# basic_circuit.net
KiCad netlist of a schematic drawn in EAGLE
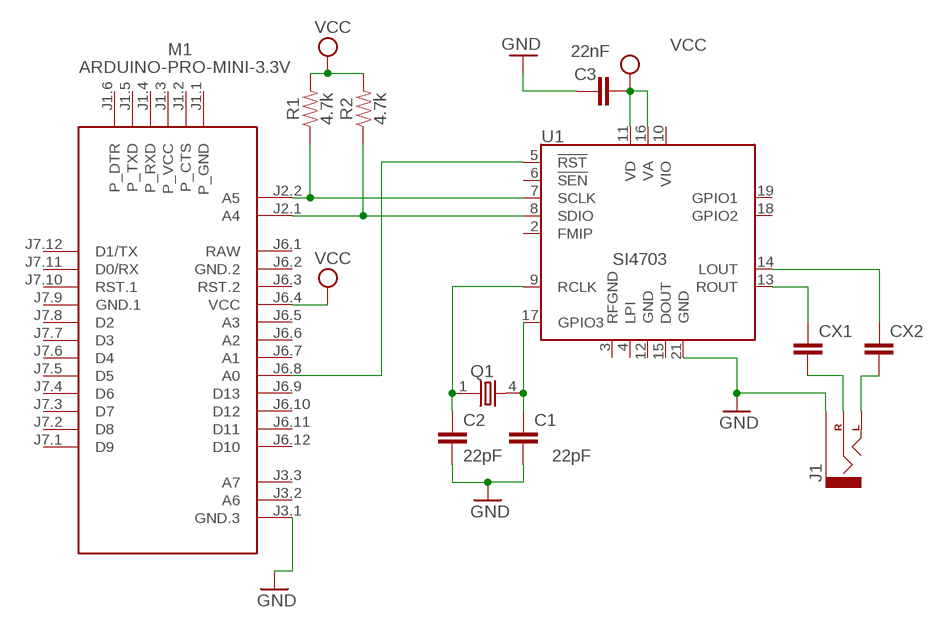
[diagram p0: schematic, sheet 1]

(export (version "E")
  (design (tool "Eeschema 10.0.6"))
  (components
    (comp (ref "C1")
      (value "22pF")
      (footprint "eagle-import:C2.5-3")
      (libsource (lib "eagle-import") (part "C2,5-3"))
    )
    (comp (ref "C2")
      (value "22pF")
      (footprint "eagle-import:C2.5-3")
      (libsource (lib "eagle-import") (part "C2,5-3"))
    )
    (comp (ref "C3")
      (value "22nF")
      (footprint "eagle-import:C2.5-3")
      (libsource (lib "eagle-import") (part "C2,5-3"))
    )
    (comp (ref "CX1")
      (value "CXXC10B6")
      (footprint "eagle-import:XC10B6")
      (libsource (lib "eagle-import") (part "CXXC10B6"))
    )
    (comp (ref "CX2")
      (value "CXXC10B6")
      (footprint "eagle-import:XC10B6")
      (libsource (lib "eagle-import") (part "CXXC10B6"))
    )
    (comp (ref "J1")
      (value "AUDIO_JACK_2.5MM_HOLESONLY")
      (footprint "eagle-import:STEREOJACK2.5MM_SPECIAL_HOLES-ONLY")
      (libsource (lib "eagle-import") (part "AUDIO_JACK_2.5MM_HOLESONLY"))
    )
    (comp (ref "M1")
      (value "ARDUINO-PRO-MINI-3.3V")
      (footprint "eagle-import:ARDUINO-PRO-MINI")
      (libsource (lib "eagle-import") (part "ARDUINO-PRO-MINI-3.3V"))
    )
    (comp (ref "Q1")
      (value "86SMX")
      (footprint "eagle-import:86SMX")
      (fields (field (name "MF") "C-MAC  FREQUENCY PRODUCTS LTD") (field (name "MPN") "XTAL003321- 86SMX"))
      (libsource (lib "eagle-import") (part "86SMX"))
    )
    (comp (ref "R1")
      (value "4.7k")
      (footprint "eagle-import:0603")
      (libsource (lib "eagle-import") (part "4.7KOHM-0603-1/10W-1%"))
    )
    (comp (ref "R2")
      (value "4.7k")
      (footprint "eagle-import:0603")
      (libsource (lib "eagle-import") (part "4.7KOHM-0603-1/10W-1%"))
    )
    (comp (ref "U1")
      (value "SI4703")
      (footprint "eagle-import:QFN-20-3X3MM")
      (fields (field (name "MF") "SparkFun Electronics"))
      (libsource (lib "eagle-import") (part "SI4703"))
    )
  )
  (nets
    (net (code "1") (name "/GND.1") (class "Default")
      (node (ref "M1") (pin "J7.9") (pinfunction "GND.1_J7.9") (pintype "power_in"))
    )
    (net (code "2") (name "/GND.2") (class "Default")
      (node (ref "M1") (pin "J6.2") (pinfunction "GND.2_J6.2") (pintype "power_in"))
    )
    (net (code "3") (name "/RAW") (class "Default")
      (node (ref "M1") (pin "J6.1") (pinfunction "RAW_J6.1") (pintype "power_in"))
    )
    (net (code "4") (name "GND") (class "Default")
      (node (ref "C1") (pin "2") (pinfunction "2_2") (pintype "passive"))
      (node (ref "C2") (pin "2") (pinfunction "2_2") (pintype "passive"))
      (node (ref "C3") (pin "1") (pinfunction "1_1") (pintype "passive"))
      (node (ref "J1") (pin "RING1") (pinfunction "SLEEVE_RING1") (pintype "bidirectional"))
      (node (ref "M1") (pin "J3.1") (pinfunction "GND.3_J3.1") (pintype "bidirectional"))
      (node (ref "U1") (pin "21") (pinfunction "GND_21") (pintype "bidirectional"))
    )
    (net (code "5") (name "Net-(J1-LEFT)") (class "Default")
      (node (ref "CX2") (pin "2") (pinfunction "2_2") (pintype "passive"))
      (node (ref "J1") (pin "SHIELD") (pinfunction "LEFT_SHIELD") (pintype "bidirectional"))
    )
    (net (code "6") (name "Net-(J1-RIGHT)") (class "Default")
      (node (ref "CX1") (pin "2") (pinfunction "2_2") (pintype "passive"))
      (node (ref "J1") (pin "TIP") (pinfunction "RIGHT_TIP") (pintype "bidirectional"))
    )
    (net (code "7") (name "Net-(M1-A0)") (class "Default")
      (node (ref "M1") (pin "J6.8") (pinfunction "A0_J6.8") (pintype "bidirectional"))
      (node (ref "U1") (pin "5") (pinfunction "~{RST}_5") (pintype "bidirectional"))
    )
    (net (code "8") (name "Net-(M1-A4)") (class "Default")
      (node (ref "M1") (pin "J2.1") (pinfunction "A4_J2.1") (pintype "bidirectional"))
      (node (ref "R2") (pin "1") (pinfunction "1_1") (pintype "passive"))
      (node (ref "U1") (pin "8") (pinfunction "SDIO_8") (pintype "bidirectional"))
    )
    (net (code "9") (name "Net-(M1-A5)") (class "Default")
      (node (ref "M1") (pin "J2.2") (pinfunction "A5_J2.2") (pintype "bidirectional"))
      (node (ref "R1") (pin "1") (pinfunction "1_1") (pintype "passive"))
      (node (ref "U1") (pin "7") (pinfunction "SCLK_7") (pintype "bidirectional"))
    )
    (net (code "10") (name "Net-(Q1-2)") (class "Default")
      (node (ref "C1") (pin "1") (pinfunction "1_1") (pintype "passive"))
      (node (ref "Q1") (pin "4") (pinfunction "2_4") (pintype "passive"))
      (node (ref "U1") (pin "17") (pinfunction "GPIO3_17") (pintype "bidirectional"))
    )
    (net (code "11") (name "Net-(U1-LOUT)") (class "Default")
      (node (ref "CX2") (pin "1") (pinfunction "1_1") (pintype "passive"))
      (node (ref "U1") (pin "14") (pinfunction "LOUT_14") (pintype "bidirectional"))
    )
    (net (code "12") (name "Net-(U1-RCLK)") (class "Default")
      (node (ref "C2") (pin "1") (pinfunction "1_1") (pintype "passive"))
      (node (ref "Q1") (pin "1") (pinfunction "1_1") (pintype "passive"))
      (node (ref "U1") (pin "9") (pinfunction "RCLK_9") (pintype "bidirectional"))
    )
    (net (code "13") (name "Net-(U1-ROUT)") (class "Default")
      (node (ref "CX1") (pin "1") (pinfunction "1_1") (pintype "passive"))
      (node (ref "U1") (pin "13") (pinfunction "ROUT_13") (pintype "bidirectional"))
    )
    (net (code "14") (name "VCC") (class "Default")
      (node (ref "C3") (pin "2") (pinfunction "2_2") (pintype "passive"))
      (node (ref "M1") (pin "J6.4") (pinfunction "VCC_J6.4") (pintype "power_in"))
      (node (ref "R1") (pin "2") (pinfunction "2_2") (pintype "passive"))
      (node (ref "R2") (pin "2") (pinfunction "2_2") (pintype "passive"))
      (node (ref "U1") (pin "11") (pinfunction "VD_11") (pintype "bidirectional"))
      (node (ref "U1") (pin "16") (pinfunction "VA_16") (pintype "bidirectional"))
    )
    (net (code "15") (name "unconnected-(M1-A1-PadJ6.7)") (class "Default")
      (node (ref "M1") (pin "J6.7") (pinfunction "A1_J6.7") (pintype "bidirectional"))
    )
    (net (code "16") (name "unconnected-(M1-A2-PadJ6.6)") (class "Default")
      (node (ref "M1") (pin "J6.6") (pinfunction "A2_J6.6") (pintype "bidirectional"))
    )
    (net (code "17") (name "unconnected-(M1-A3-PadJ6.5)") (class "Default")
      (node (ref "M1") (pin "J6.5") (pinfunction "A3_J6.5") (pintype "bidirectional"))
    )
    (net (code "18") (name "unconnected-(M1-A6-PadJ3.2)") (class "Default")
      (node (ref "M1") (pin "J3.2") (pinfunction "A6_J3.2") (pintype "bidirectional"))
    )
    (net (code "19") (name "unconnected-(M1-A7-PadJ3.3)") (class "Default")
      (node (ref "M1") (pin "J3.3") (pinfunction "A7_J3.3") (pintype "bidirectional"))
    )
    (net (code "20") (name "unconnected-(M1-D0{slash}RX-PadJ7.11)") (class "Default")
      (node (ref "M1") (pin "J7.11") (pinfunction "D0/RX_J7.11") (pintype "bidirectional"))
    )
    (net (code "21") (name "unconnected-(M1-D1{slash}TX-PadJ7.12)") (class "Default")
      (node (ref "M1") (pin "J7.12") (pinfunction "D1/TX_J7.12") (pintype "bidirectional"))
    )
    (net (code "22") (name "unconnected-(M1-D2-PadJ7.8)") (class "Default")
      (node (ref "M1") (pin "J7.8") (pinfunction "D2_J7.8") (pintype "bidirectional"))
    )
    (net (code "23") (name "unconnected-(M1-D3-PadJ7.7)") (class "Default")
      (node (ref "M1") (pin "J7.7") (pinfunction "D3_J7.7") (pintype "bidirectional"))
    )
    (net (code "24") (name "unconnected-(M1-D4-PadJ7.6)") (class "Default")
      (node (ref "M1") (pin "J7.6") (pinfunction "D4_J7.6") (pintype "bidirectional"))
    )
    (net (code "25") (name "unconnected-(M1-D5-PadJ7.5)") (class "Default")
      (node (ref "M1") (pin "J7.5") (pinfunction "D5_J7.5") (pintype "bidirectional"))
    )
    (net (code "26") (name "unconnected-(M1-D6-PadJ7.4)") (class "Default")
      (node (ref "M1") (pin "J7.4") (pinfunction "D6_J7.4") (pintype "bidirectional"))
    )
    (net (code "27") (name "unconnected-(M1-D7-PadJ7.3)") (class "Default")
      (node (ref "M1") (pin "J7.3") (pinfunction "D7_J7.3") (pintype "bidirectional"))
    )
    (net (code "28") (name "unconnected-(M1-D8-PadJ7.2)") (class "Default")
      (node (ref "M1") (pin "J7.2") (pinfunction "D8_J7.2") (pintype "bidirectional"))
    )
    (net (code "29") (name "unconnected-(M1-D9-PadJ7.1)") (class "Default")
      (node (ref "M1") (pin "J7.1") (pinfunction "D9_J7.1") (pintype "bidirectional"))
    )
    (net (code "30") (name "unconnected-(M1-D10-PadJ6.12)") (class "Default")
      (node (ref "M1") (pin "J6.12") (pinfunction "D10_J6.12") (pintype "bidirectional"))
    )
    (net (code "31") (name "unconnected-(M1-D11-PadJ6.11)") (class "Default")
      (node (ref "M1") (pin "J6.11") (pinfunction "D11_J6.11") (pintype "bidirectional"))
    )
    (net (code "32") (name "unconnected-(M1-D12-PadJ6.10)") (class "Default")
      (node (ref "M1") (pin "J6.10") (pinfunction "D12_J6.10") (pintype "bidirectional"))
    )
    (net (code "33") (name "unconnected-(M1-D13-PadJ6.9)") (class "Default")
      (node (ref "M1") (pin "J6.9") (pinfunction "D13_J6.9") (pintype "bidirectional"))
    )
    (net (code "34") (name "unconnected-(M1-P_CTS-PadJ1.2)") (class "Default")
      (node (ref "M1") (pin "J1.2") (pinfunction "P_CTS_J1.2") (pintype "bidirectional"))
    )
    (net (code "35") (name "unconnected-(M1-P_DTR-PadJ1.6)") (class "Default")
      (node (ref "M1") (pin "J1.6") (pinfunction "P_DTR_J1.6") (pintype "bidirectional"))
    )
    (net (code "36") (name "unconnected-(M1-P_GND-PadJ1.1)") (class "Default")
      (node (ref "M1") (pin "J1.1") (pinfunction "P_GND_J1.1") (pintype "bidirectional"))
    )
    (net (code "37") (name "unconnected-(M1-P_RXD-PadJ1.4)") (class "Default")
      (node (ref "M1") (pin "J1.4") (pinfunction "P_RXD_J1.4") (pintype "bidirectional"))
    )
    (net (code "38") (name "unconnected-(M1-P_TXD-PadJ1.5)") (class "Default")
      (node (ref "M1") (pin "J1.5") (pinfunction "P_TXD_J1.5") (pintype "bidirectional"))
    )
    (net (code "39") (name "unconnected-(M1-P_VCC-PadJ1.3)") (class "Default")
      (node (ref "M1") (pin "J1.3") (pinfunction "P_VCC_J1.3") (pintype "bidirectional"))
    )
    (net (code "40") (name "unconnected-(M1-RST.1-PadJ7.10)") (class "Default")
      (node (ref "M1") (pin "J7.10") (pinfunction "RST.1_J7.10") (pintype "bidirectional"))
    )
    (net (code "41") (name "unconnected-(M1-RST.2-PadJ6.3)") (class "Default")
      (node (ref "M1") (pin "J6.3") (pinfunction "RST.2_J6.3") (pintype "bidirectional"))
    )
    (net (code "42") (name "unconnected-(U1-DOUT-Pad15)") (class "Default")
      (node (ref "U1") (pin "15") (pinfunction "DOUT_15") (pintype "bidirectional"))
    )
    (net (code "43") (name "unconnected-(U1-FMIP-Pad2)") (class "Default")
      (node (ref "U1") (pin "2") (pinfunction "FMIP_2") (pintype "bidirectional"))
    )
    (net (code "44") (name "unconnected-(U1-GND-Pad12)") (class "Default")
      (node (ref "U1") (pin "12") (pinfunction "GND_12") (pintype "bidirectional"))
    )
    (net (code "45") (name "unconnected-(U1-GPIO1-Pad19)") (class "Default")
      (node (ref "U1") (pin "19") (pinfunction "GPIO1_19") (pintype "bidirectional"))
    )
    (net (code "46") (name "unconnected-(U1-GPIO2-Pad18)") (class "Default")
      (node (ref "U1") (pin "18") (pinfunction "GPIO2_18") (pintype "bidirectional"))
    )
    (net (code "47") (name "unconnected-(U1-LPI-Pad4)") (class "Default")
      (node (ref "U1") (pin "4") (pinfunction "LPI_4") (pintype "bidirectional"))
    )
    (net (code "48") (name "unconnected-(U1-RFGND-Pad3)") (class "Default")
      (node (ref "U1") (pin "3") (pinfunction "RFGND_3") (pintype "bidirectional"))
    )
    (net (code "49") (name "unconnected-(U1-VIO-Pad10)") (class "Default")
      (node (ref "U1") (pin "10") (pinfunction "VIO_10") (pintype "bidirectional"))
    )
    (net (code "50") (name "unconnected-(U1-~{SEN}-Pad6)") (class "Default")
      (node (ref "U1") (pin "6") (pinfunction "~{SEN}_6") (pintype "bidirectional"))
    )
  )
)
